# Sheet1.net
KiCad netlist of a schematic drawn in Altium Designer
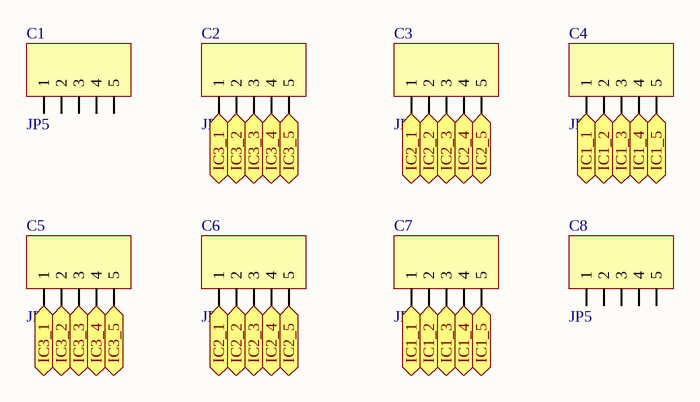
[diagram p0: Sheet1.SchDoc]

(export (version "E")
  (design (tool "Eeschema 10.0.6"))
  (components
    (comp (ref "C1")
      (value "JP5")
      (footprint "JP5-D1T")
      (description "WR-PHD 2.54 mm Angled Socket Header")
      (fields
        (field (name "MANUFACTURER") "Würth Elektronik eiSos GmbH")
        (field (name "PARTNO") "613005143121")
        (field (name "CREATED BY") "Karrer Zheng")
      )
      (libsource (lib "LIBRARY") (part "JP5"))
    )
    (comp (ref "C2")
      (value "JP5")
      (footprint "JP5-D1T")
      (description "WR-PHD 2.54 mm Angled Socket Header")
      (fields
        (field (name "MANUFACTURER") "Würth Elektronik eiSos GmbH")
        (field (name "PARTNO") "613005143121")
        (field (name "CREATED BY") "Karrer Zheng")
      )
      (libsource (lib "LIBRARY") (part "JP5"))
    )
    (comp (ref "C3")
      (value "JP5")
      (footprint "JP5-D1T")
      (description "WR-PHD 2.54 mm Angled Socket Header")
      (fields
        (field (name "MANUFACTURER") "Würth Elektronik eiSos GmbH")
        (field (name "PARTNO") "613005143121")
        (field (name "CREATED BY") "Karrer Zheng")
      )
      (libsource (lib "LIBRARY") (part "JP5"))
    )
    (comp (ref "C4")
      (value "JP5")
      (footprint "JP5-D1T")
      (description "WR-PHD 2.54 mm Angled Socket Header")
      (fields
        (field (name "MANUFACTURER") "Würth Elektronik eiSos GmbH")
        (field (name "PARTNO") "613005143121")
        (field (name "CREATED BY") "Karrer Zheng")
      )
      (libsource (lib "LIBRARY") (part "JP5"))
    )
    (comp (ref "C5")
      (value "JP5")
      (footprint "JP5-D1T")
      (description "WR-PHD 2.54 mm Angled Socket Header")
      (fields
        (field (name "MANUFACTURER") "Würth Elektronik eiSos GmbH")
        (field (name "PARTNO") "613005143121")
        (field (name "CREATED BY") "Karrer Zheng")
      )
      (libsource (lib "LIBRARY") (part "JP5"))
    )
    (comp (ref "C6")
      (value "JP5")
      (footprint "JP5-D1T")
      (description "WR-PHD 2.54 mm Angled Socket Header")
      (fields
        (field (name "MANUFACTURER") "Würth Elektronik eiSos GmbH")
        (field (name "PARTNO") "613005143121")
        (field (name "CREATED BY") "Karrer Zheng")
      )
      (libsource (lib "LIBRARY") (part "JP5"))
    )
    (comp (ref "C7")
      (value "JP5")
      (footprint "JP5-D1T")
      (description "WR-PHD 2.54 mm Angled Socket Header")
      (fields
        (field (name "MANUFACTURER") "Würth Elektronik eiSos GmbH")
        (field (name "PARTNO") "613005143121")
        (field (name "CREATED BY") "Karrer Zheng")
      )
      (libsource (lib "LIBRARY") (part "JP5"))
    )
    (comp (ref "C8")
      (value "JP5")
      (footprint "JP5-D1T")
      (description "WR-PHD 2.54 mm Angled Socket Header")
      (fields
        (field (name "MANUFACTURER") "Würth Elektronik eiSos GmbH")
        (field (name "PARTNO") "613005143121")
        (field (name "CREATED BY") "Karrer Zheng")
      )
      (libsource (lib "LIBRARY") (part "JP5"))
    )
  )
  (nets
    (net (code "1") (name "/IC1_1") (class "Default")
      (node (ref "C4") (pin "1") (pinfunction "1_1") (pintype "passive"))
      (node (ref "C7") (pin "1") (pinfunction "1_1") (pintype "passive"))
    )
    (net (code "2") (name "/IC1_2") (class "Default")
      (node (ref "C4") (pin "2") (pinfunction "2_2") (pintype "passive"))
      (node (ref "C7") (pin "2") (pinfunction "2_2") (pintype "passive"))
    )
    (net (code "3") (name "/IC1_3") (class "Default")
      (node (ref "C4") (pin "3") (pinfunction "3_3") (pintype "passive"))
      (node (ref "C7") (pin "3") (pinfunction "3_3") (pintype "passive"))
    )
    (net (code "4") (name "/IC1_4") (class "Default")
      (node (ref "C4") (pin "4") (pinfunction "4_4") (pintype "passive"))
      (node (ref "C7") (pin "4") (pinfunction "4_4") (pintype "passive"))
    )
    (net (code "5") (name "/IC1_5") (class "Default")
      (node (ref "C4") (pin "5") (pinfunction "5_5") (pintype "passive"))
      (node (ref "C7") (pin "5") (pinfunction "5_5") (pintype "passive"))
    )
    (net (code "6") (name "/IC2_1") (class "Default")
      (node (ref "C3") (pin "1") (pinfunction "1_1") (pintype "passive"))
      (node (ref "C6") (pin "1") (pinfunction "1_1") (pintype "passive"))
    )
    (net (code "7") (name "/IC2_2") (class "Default")
      (node (ref "C3") (pin "2") (pinfunction "2_2") (pintype "passive"))
      (node (ref "C6") (pin "2") (pinfunction "2_2") (pintype "passive"))
    )
    (net (code "8") (name "/IC2_3") (class "Default")
      (node (ref "C3") (pin "3") (pinfunction "3_3") (pintype "passive"))
      (node (ref "C6") (pin "3") (pinfunction "3_3") (pintype "passive"))
    )
    (net (code "9") (name "/IC2_4") (class "Default")
      (node (ref "C3") (pin "4") (pinfunction "4_4") (pintype "passive"))
      (node (ref "C6") (pin "4") (pinfunction "4_4") (pintype "passive"))
    )
    (net (code "10") (name "/IC2_5") (class "Default")
      (node (ref "C3") (pin "5") (pinfunction "5_5") (pintype "passive"))
      (node (ref "C6") (pin "5") (pinfunction "5_5") (pintype "passive"))
    )
    (net (code "11") (name "/IC3_1") (class "Default")
      (node (ref "C2") (pin "1") (pinfunction "1_1") (pintype "passive"))
      (node (ref "C5") (pin "1") (pinfunction "1_1") (pintype "passive"))
    )
    (net (code "12") (name "/IC3_2") (class "Default")
      (node (ref "C2") (pin "2") (pinfunction "2_2") (pintype "passive"))
      (node (ref "C5") (pin "2") (pinfunction "2_2") (pintype "passive"))
    )
    (net (code "13") (name "/IC3_3") (class "Default")
      (node (ref "C2") (pin "3") (pinfunction "3_3") (pintype "passive"))
      (node (ref "C5") (pin "3") (pinfunction "3_3") (pintype "passive"))
    )
    (net (code "14") (name "/IC3_4") (class "Default")
      (node (ref "C2") (pin "4") (pinfunction "4_4") (pintype "passive"))
      (node (ref "C5") (pin "4") (pinfunction "4_4") (pintype "passive"))
    )
    (net (code "15") (name "/IC3_5") (class "Default")
      (node (ref "C2") (pin "5") (pinfunction "5_5") (pintype "passive"))
      (node (ref "C5") (pin "5") (pinfunction "5_5") (pintype "passive"))
    )
    (net (code "16") (name "unconnected-(C1-Pad1)") (class "Default")
      (node (ref "C1") (pin "1") (pinfunction "1_1") (pintype "passive"))
    )
    (net (code "17") (name "unconnected-(C1-Pad2)") (class "Default")
      (node (ref "C1") (pin "2") (pinfunction "2_2") (pintype "passive"))
    )
    (net (code "18") (name "unconnected-(C1-Pad3)") (class "Default")
      (node (ref "C1") (pin "3") (pinfunction "3_3") (pintype "passive"))
    )
    (net (code "19") (name "unconnected-(C1-Pad4)") (class "Default")
      (node (ref "C1") (pin "4") (pinfunction "4_4") (pintype "passive"))
    )
    (net (code "20") (name "unconnected-(C1-Pad5)") (class "Default")
      (node (ref "C1") (pin "5") (pinfunction "5_5") (pintype "passive"))
    )
    (net (code "21") (name "unconnected-(C8-Pad1)") (class "Default")
      (node (ref "C8") (pin "1") (pinfunction "1_1") (pintype "passive"))
    )
    (net (code "22") (name "unconnected-(C8-Pad2)") (class "Default")
      (node (ref "C8") (pin "2") (pinfunction "2_2") (pintype "passive"))
    )
    (net (code "23") (name "unconnected-(C8-Pad3)") (class "Default")
      (node (ref "C8") (pin "3") (pinfunction "3_3") (pintype "passive"))
    )
    (net (code "24") (name "unconnected-(C8-Pad4)") (class "Default")
      (node (ref "C8") (pin "4") (pinfunction "4_4") (pintype "passive"))
    )
    (net (code "25") (name "unconnected-(C8-Pad5)") (class "Default")
      (node (ref "C8") (pin "5") (pinfunction "5_5") (pintype "passive"))
    )
  )
)
